# coils.net
KiCad netlist of a schematic drawn in Altium Designer
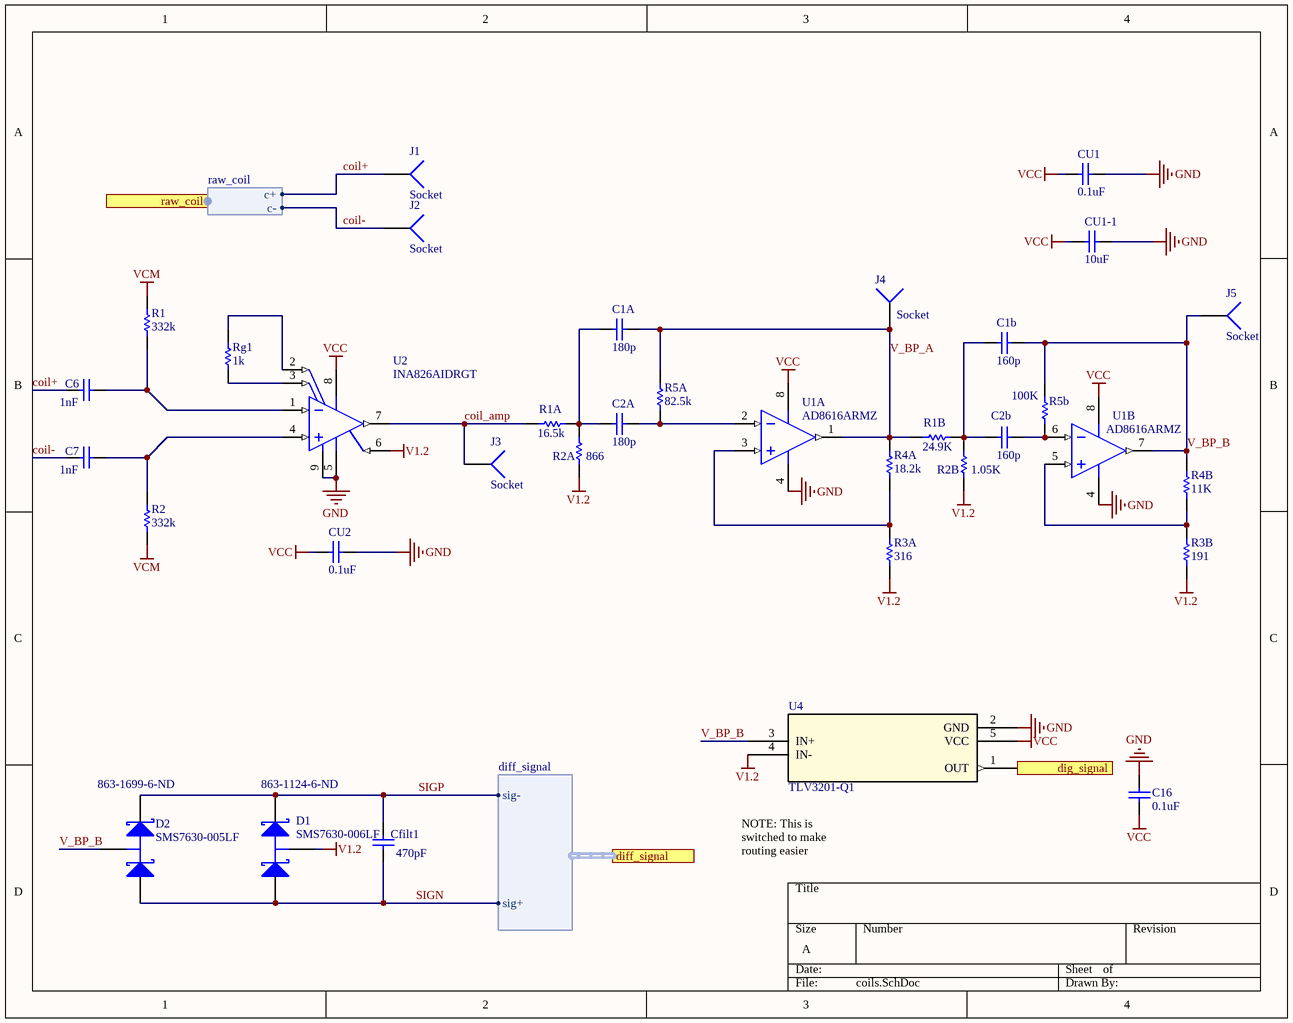
[diagram p0: coils.SchDoc]

(export (version "E")
  (design (tool "Eeschema 10.0.6"))
  (components
    (comp (ref "C1A")
      (value "180p")
      (footprint "0402")
      (description "Ceramic Capacitor (Surface Mount)")
      (fields (field (name "MANUFACTURER") "Generic Ceramic Chip Cap (TBD)") (field (name "Comment") "Cap"))
      (libsource (lib "maglib") (part "Cap"))
    )
    (comp (ref "C1b")
      (value "160p")
      (footprint "0402")
      (description "Ceramic Capacitor (Surface Mount)")
      (fields (field (name "MANUFACTURER") "Generic Ceramic Chip Cap (TBD)") (field (name "Comment") "Cap"))
      (libsource (lib "maglib") (part "Cap"))
    )
    (comp (ref "C2A")
      (value "180p")
      (footprint "0402")
      (description "Ceramic Capacitor (Surface Mount)")
      (fields (field (name "MANUFACTURER") "Generic Ceramic Chip Cap (TBD)") (field (name "Comment") "Cap"))
      (libsource (lib "maglib") (part "Cap"))
    )
    (comp (ref "C2b")
      (value "160p")
      (footprint "0402")
      (description "Ceramic Capacitor (Surface Mount)")
      (fields (field (name "MANUFACTURER") "Generic Ceramic Chip Cap (TBD)") (field (name "Comment") "Cap"))
      (libsource (lib "maglib") (part "Cap"))
    )
    (comp (ref "C6")
      (value "1nF")
      (footprint "0402")
      (description "Ceramic Capacitor (Surface Mount)")
      (fields (field (name "MANUFACTURER") "Generic Ceramic Chip Cap (TBD)") (field (name "Comment") "Cap"))
      (libsource (lib "maglib") (part "Cap"))
    )
    (comp (ref "C7")
      (value "1nF")
      (footprint "0402")
      (description "Ceramic Capacitor (Surface Mount)")
      (fields (field (name "MANUFACTURER") "Generic Ceramic Chip Cap (TBD)") (field (name "Comment") "Cap"))
      (libsource (lib "maglib") (part "Cap"))
    )
    (comp (ref "C16")
      (value "0.1uF")
      (footprint "0402")
      (description "Ceramic Capacitor (Surface Mount)")
      (fields (field (name "MANUFACTURER") "Generic Ceramic Chip Cap (TBD)") (field (name "Comment") "Cap"))
      (libsource (lib "maglib") (part "Cap"))
    )
    (comp (ref "Cfilt1")
      (value "470pF")
      (footprint "0402")
      (description "Ceramic Capacitor (Surface Mount)")
      (fields (field (name "MANUFACTURER") "Generic Ceramic Chip Cap (TBD)") (field (name "Comment") "Cap"))
      (libsource (lib "maglib") (part "Cap"))
    )
    (comp (ref "CU1")
      (value "0.1uF")
      (footprint "0402")
      (description "Ceramic Capacitor (Surface Mount)")
      (fields (field (name "MANUFACTURER") "Generic Ceramic Chip Cap (TBD)") (field (name "Comment") "Cap"))
      (libsource (lib "maglib") (part "Cap"))
    )
    (comp (ref "CU1-1")
      (value "10uF")
      (footprint "0402")
      (description "Ceramic Capacitor (Surface Mount)")
      (fields (field (name "MANUFACTURER") "Generic Ceramic Chip Cap (TBD)") (field (name "Comment") "Cap"))
      (libsource (lib "maglib") (part "Cap"))
    )
    (comp (ref "CU2")
      (value "0.1uF")
      (footprint "0402")
      (description "Ceramic Capacitor (Surface Mount)")
      (fields (field (name "MANUFACTURER") "Generic Ceramic Chip Cap (TBD)") (field (name "Comment") "Cap"))
      (libsource (lib "maglib") (part "Cap"))
    )
    (comp (ref "D1")
      (value "SMS7630-006LF")
      (footprint "SOT23-3N")
      (fields (field (name "SUPPLIER PART NUMBER 1") "863-1124-6-ND"))
      (libsource (lib "maglib") (part "SMS7621-006LF"))
    )
    (comp (ref "D2")
      (value "SMS7630-005LF")
      (footprint "SOT23-3N")
      (fields (field (name "SUPPLIER PART NUMBER 1") "863-1699-6-ND"))
      (libsource (lib "maglib") (part "SMS7621-005LF"))
    )
    (comp (ref "J1")
      (value "Socket")
      (footprint "pin1")
      (fields (field (name "PUBLISHER") "Altium Limited"))
      (libsource (lib "tx") (part "Socket"))
    )
    (comp (ref "J2")
      (value "Socket")
      (footprint "pin1")
      (fields (field (name "PUBLISHER") "Altium Limited"))
      (libsource (lib "Miscellaneous Connectors") (part "Socket"))
    )
    (comp (ref "J3")
      (value "Socket")
      (footprint "pin1")
      (fields (field (name "PUBLISHER") "Altium Limited"))
      (libsource (lib "Miscellaneous Connectors") (part "Socket"))
    )
    (comp (ref "J4")
      (value "Socket")
      (footprint "pin1")
      (fields (field (name "PUBLISHER") "Altium Limited"))
      (libsource (lib "Miscellaneous Connectors") (part "Socket"))
    )
    (comp (ref "J5")
      (value "Socket")
      (footprint "pin1")
      (fields (field (name "PUBLISHER") "Altium Limited"))
      (libsource (lib "Miscellaneous Connectors") (part "Socket"))
    )
    (comp (ref "R1")
      (value "332k")
      (footprint "0402")
      (description "Chip Resistor (Surface Mount)")
      (fields (field (name "MANUFACTURER") "Generic Chip Res (TBD)") (field (name "Comment") "Res"))
      (libsource (lib "maglib") (part "Res"))
    )
    (comp (ref "R1A")
      (value "16.5k")
      (footprint "0402")
      (description "Chip Resistor (Surface Mount)")
      (fields (field (name "MANUFACTURER") "Generic Chip Res (TBD)") (field (name "Comment") "Res"))
      (libsource (lib "maglib") (part "Res"))
    )
    (comp (ref "R1B")
      (value "24.9K")
      (footprint "0402")
      (description "Chip Resistor (Surface Mount)")
      (fields (field (name "MANUFACTURER") "Generic Chip Res (TBD)") (field (name "Comment") "Res"))
      (libsource (lib "maglib") (part "Res"))
    )
    (comp (ref "R2")
      (value "332k")
      (footprint "0402")
      (description "Chip Resistor (Surface Mount)")
      (fields (field (name "MANUFACTURER") "Generic Chip Res (TBD)") (field (name "Comment") "Res"))
      (libsource (lib "maglib") (part "Res"))
    )
    (comp (ref "R2A")
      (value "866")
      (footprint "0402")
      (description "Chip Resistor (Surface Mount)")
      (fields (field (name "MANUFACTURER") "Generic Chip Res (TBD)") (field (name "Comment") "Res"))
      (libsource (lib "maglib") (part "Res"))
    )
    (comp (ref "R2B")
      (value "1.05K")
      (footprint "0402")
      (description "Chip Resistor (Surface Mount)")
      (fields (field (name "MANUFACTURER") "Generic Chip Res (TBD)") (field (name "Comment") "Res"))
      (libsource (lib "maglib") (part "Res"))
    )
    (comp (ref "R3A")
      (value "316")
      (footprint "0402")
      (description "Chip Resistor (Surface Mount)")
      (fields (field (name "MANUFACTURER") "Generic Chip Res (TBD)") (field (name "Comment") "Res"))
      (libsource (lib "maglib") (part "Res"))
    )
    (comp (ref "R3B")
      (value "191")
      (footprint "0402")
      (description "Chip Resistor (Surface Mount)")
      (fields (field (name "MANUFACTURER") "Generic Chip Res (TBD)") (field (name "Comment") "Res"))
      (libsource (lib "maglib") (part "Res"))
    )
    (comp (ref "R4A")
      (value "18.2k")
      (footprint "0402")
      (description "Chip Resistor (Surface Mount)")
      (fields (field (name "MANUFACTURER") "Generic Chip Res (TBD)") (field (name "Comment") "Res"))
      (libsource (lib "maglib") (part "Res"))
    )
    (comp (ref "R4B")
      (value "11K")
      (footprint "0402")
      (description "Chip Resistor (Surface Mount)")
      (fields (field (name "MANUFACTURER") "Generic Chip Res (TBD)") (field (name "Comment") "Res"))
      (libsource (lib "maglib") (part "Res"))
    )
    (comp (ref "R5A")
      (value "82.5k")
      (footprint "0402")
      (description "Chip Resistor (Surface Mount)")
      (fields (field (name "MANUFACTURER") "Generic Chip Res (TBD)") (field (name "Comment") "Res"))
      (libsource (lib "maglib") (part "Res"))
    )
    (comp (ref "R5b")
      (value "100K")
      (footprint "0402")
      (description "Chip Resistor (Surface Mount)")
      (fields (field (name "MANUFACTURER") "Generic Chip Res (TBD)") (field (name "Comment") "Res"))
      (libsource (lib "maglib") (part "Res"))
    )
    (comp (ref "Rg1")
      (value "1k")
      (footprint "0402")
      (description "Chip Resistor (Surface Mount)")
      (fields (field (name "MANUFACTURER") "Generic Chip Res (TBD)") (field (name "Comment") "Res"))
      (libsource (lib "maglib") (part "Res"))
    )
    (comp (ref "U1")
      (value "AD8616ARMZ")
      (footprint "ADI-RM-8_N")
      (fields (field (name "GENERIC PART NUMBER") "AD8616") (field (name "MANUFACTURER") "Analog Devices"))
      (libsource (lib "Altium Content Vault") (part "ADI-OP29X-R-8"))
    )
    (comp (ref "U2")
      (value "INA826AIDRGT")
      (footprint "DRG0008A_V")
      (fields (field (name "MANUFACTURER") "Texas Instruments"))
      (libsource (lib "Altium Content Vault") (part "TI-INA826DRG8-2000X1200TP"))
    )
    (comp (ref "U4")
      (value "TLV3201-Q1")
      (footprint "SOT95P280X145-5N")
      (description "40-ns, Micropower Comparator")
      (libsource (lib "maglib") (part "TLV3201-Q1"))
    )
  )
  (nets
    (net (code "3") (name "/SIGN") (class "Default")
      (node (ref "Cfilt1") (pin "1") (pinfunction "1_1") (pintype "passive"))
      (node (ref "D1") (pin "2") (pinfunction "K_2") (pintype "passive"))
      (node (ref "D2") (pin "1") (pinfunction "A_1") (pintype "passive"))
    )
    (net (code "4") (name "/SIGP") (class "Default")
      (node (ref "Cfilt1") (pin "2") (pinfunction "2_2") (pintype "passive"))
      (node (ref "D1") (pin "1") (pinfunction "A_1") (pintype "passive"))
      (node (ref "D2") (pin "2") (pinfunction "K_2") (pintype "passive"))
    )
    (net (code "5") (name "/V_BP_A") (class "Default")
      (node (ref "C1A") (pin "2") (pinfunction "2_2") (pintype "passive"))
      (node (ref "J4") (pin "1") (pinfunction "1_1") (pintype "passive"))
      (node (ref "R1B") (pin "1") (pinfunction "1_1") (pintype "passive"))
      (node (ref "R4A") (pin "1") (pinfunction "1_1") (pintype "passive"))
      (node (ref "R5A") (pin "1") (pinfunction "1_1") (pintype "passive"))
      (node (ref "U1") (pin "1") (pinfunction "OUT_A_1") (pintype "output"))
    )
    (net (code "6") (name "/V_BP_B") (class "Default")
      (node (ref "C1b") (pin "2") (pinfunction "2_2") (pintype "passive"))
      (node (ref "D2") (pin "3") (pinfunction "C_3") (pintype "passive"))
      (node (ref "J5") (pin "1") (pinfunction "1_1") (pintype "passive"))
      (node (ref "R4B") (pin "2") (pinfunction "2_2") (pintype "passive"))
      (node (ref "R5b") (pin "1") (pinfunction "1_1") (pintype "passive"))
      (node (ref "U1") (pin "7") (pinfunction "OUT_B_7") (pintype "output"))
      (node (ref "U4") (pin "3") (pinfunction "IN+_3") (pintype "passive"))
    )
    (net (code "7") (name "/coil+") (class "Default")
      (node (ref "C6") (pin "1") (pinfunction "1_1") (pintype "passive"))
      (node (ref "J1") (pin "1") (pinfunction "1_1") (pintype "passive"))
    )
    (net (code "8") (name "/coil-") (class "Default")
      (node (ref "C7") (pin "1") (pinfunction "1_1") (pintype "passive"))
      (node (ref "J2") (pin "1") (pinfunction "1_1") (pintype "passive"))
    )
    (net (code "9") (name "/coil_amp") (class "Default")
      (node (ref "J3") (pin "1") (pinfunction "1_1") (pintype "passive"))
      (node (ref "R1A") (pin "1") (pinfunction "1_1") (pintype "passive"))
      (node (ref "U2") (pin "7") (pinfunction "VOUT_7") (pintype "output"))
    )
    (net (code "10") (name "/dig_signal") (class "Default")
      (node (ref "U4") (pin "1") (pinfunction "OUT_1") (pintype "output"))
    )
    (net (code "13") (name "GND") (class "Default")
      (node (ref "C16") (pin "2") (pinfunction "2_2") (pintype "passive"))
      (node (ref "CU1") (pin "1") (pinfunction "1_1") (pintype "passive"))
      (node (ref "CU1-1") (pin "1") (pinfunction "1_1") (pintype "passive"))
      (node (ref "CU2") (pin "1") (pinfunction "1_1") (pintype "passive"))
      (node (ref "U1") (pin "4") (pinfunction "-V_4") (pintype "power_in"))
      (node (ref "U2") (pin "5") (pinfunction "VS-_5") (pintype "power_in"))
      (node (ref "U2") (pin "9") (pinfunction "EP_9") (pintype "passive"))
      (node (ref "U4") (pin "2") (pinfunction "GND_2") (pintype "power_in"))
    )
    (net (code "14") (name "Net-(C1A-Pad1)") (class "Default")
      (node (ref "C1A") (pin "1") (pinfunction "1_1") (pintype "passive"))
      (node (ref "C2A") (pin "1") (pinfunction "1_1") (pintype "passive"))
      (node (ref "R1A") (pin "2") (pinfunction "2_2") (pintype "passive"))
      (node (ref "R2A") (pin "2") (pinfunction "2_2") (pintype "passive"))
    )
    (net (code "15") (name "Net-(C1b-Pad1)") (class "Default")
      (node (ref "C1b") (pin "1") (pinfunction "1_1") (pintype "passive"))
      (node (ref "C2b") (pin "1") (pinfunction "1_1") (pintype "passive"))
      (node (ref "R1B") (pin "2") (pinfunction "2_2") (pintype "passive"))
      (node (ref "R2B") (pin "2") (pinfunction "2_2") (pintype "passive"))
    )
    (net (code "16") (name "Net-(Rg1-Pad1)") (class "Default")
      (node (ref "Rg1") (pin "1") (pinfunction "1_1") (pintype "passive"))
      (node (ref "U2") (pin "2") (pinfunction "RG_2") (pintype "input"))
    )
    (net (code "17") (name "Net-(Rg1-Pad2)") (class "Default")
      (node (ref "Rg1") (pin "2") (pinfunction "2_2") (pintype "passive"))
      (node (ref "U2") (pin "3") (pinfunction "RG_3") (pintype "input"))
    )
    (net (code "18") (name "Net-(U1A-+IN_A)") (class "Default")
      (node (ref "R3A") (pin "1") (pinfunction "1_1") (pintype "passive"))
      (node (ref "R4A") (pin "2") (pinfunction "2_2") (pintype "passive"))
      (node (ref "U1") (pin "3") (pinfunction "+IN_A_3") (pintype "input"))
    )
    (net (code "19") (name "Net-(U1A--IN_A)") (class "Default")
      (node (ref "C2A") (pin "2") (pinfunction "2_2") (pintype "passive"))
      (node (ref "R5A") (pin "2") (pinfunction "2_2") (pintype "passive"))
      (node (ref "U1") (pin "2") (pinfunction "-IN_A_2") (pintype "input"))
    )
    (net (code "20") (name "Net-(U1B-+IN_B)") (class "Default")
      (node (ref "R3B") (pin "2") (pinfunction "2_2") (pintype "passive"))
      (node (ref "R4B") (pin "1") (pinfunction "1_1") (pintype "passive"))
      (node (ref "U1") (pin "5") (pinfunction "+IN_B_5") (pintype "input"))
    )
    (net (code "21") (name "Net-(U1B--IN_B)") (class "Default")
      (node (ref "C2b") (pin "2") (pinfunction "2_2") (pintype "passive"))
      (node (ref "R5b") (pin "2") (pinfunction "2_2") (pintype "passive"))
      (node (ref "U1") (pin "6") (pinfunction "-IN_B_6") (pintype "input"))
    )
    (net (code "22") (name "Net-(U2-IN+)") (class "Default")
      (node (ref "C7") (pin "2") (pinfunction "2_2") (pintype "passive"))
      (node (ref "R2") (pin "2") (pinfunction "2_2") (pintype "passive"))
      (node (ref "U2") (pin "4") (pinfunction "IN+_4") (pintype "input"))
    )
    (net (code "23") (name "Net-(U2-IN-)") (class "Default")
      (node (ref "C6") (pin "2") (pinfunction "2_2") (pintype "passive"))
      (node (ref "R1") (pin "1") (pinfunction "1_1") (pintype "passive"))
      (node (ref "U2") (pin "1") (pinfunction "IN-_1") (pintype "input"))
    )
    (net (code "24") (name "V1.2") (class "Default")
      (node (ref "D1") (pin "3") (pinfunction "C_3") (pintype "passive"))
      (node (ref "R2A") (pin "1") (pinfunction "1_1") (pintype "passive"))
      (node (ref "R2B") (pin "1") (pinfunction "1_1") (pintype "passive"))
      (node (ref "R3A") (pin "2") (pinfunction "2_2") (pintype "passive"))
      (node (ref "R3B") (pin "1") (pinfunction "1_1") (pintype "passive"))
      (node (ref "U2") (pin "6") (pinfunction "REF_6") (pintype "input"))
      (node (ref "U4") (pin "4") (pinfunction "IN-_4") (pintype "passive"))
    )
    (net (code "25") (name "VCC") (class "Default")
      (node (ref "C16") (pin "1") (pinfunction "1_1") (pintype "passive"))
      (node (ref "CU1") (pin "2") (pinfunction "2_2") (pintype "passive"))
      (node (ref "CU1-1") (pin "2") (pinfunction "2_2") (pintype "passive"))
      (node (ref "CU2") (pin "2") (pinfunction "2_2") (pintype "passive"))
      (node (ref "U1") (pin "8") (pinfunction "+V_8") (pintype "power_in"))
      (node (ref "U2") (pin "8") (pinfunction "VS+_8") (pintype "power_in"))
      (node (ref "U4") (pin "5") (pinfunction "VCC_5") (pintype "power_in"))
    )
    (net (code "26") (name "VCM") (class "Default")
      (node (ref "R1") (pin "2") (pinfunction "2_2") (pintype "passive"))
      (node (ref "R2") (pin "1") (pinfunction "1_1") (pintype "passive"))
    )
  )
)
